# H7864.net
KiCad netlist of a schematic drawn in Altium Designer
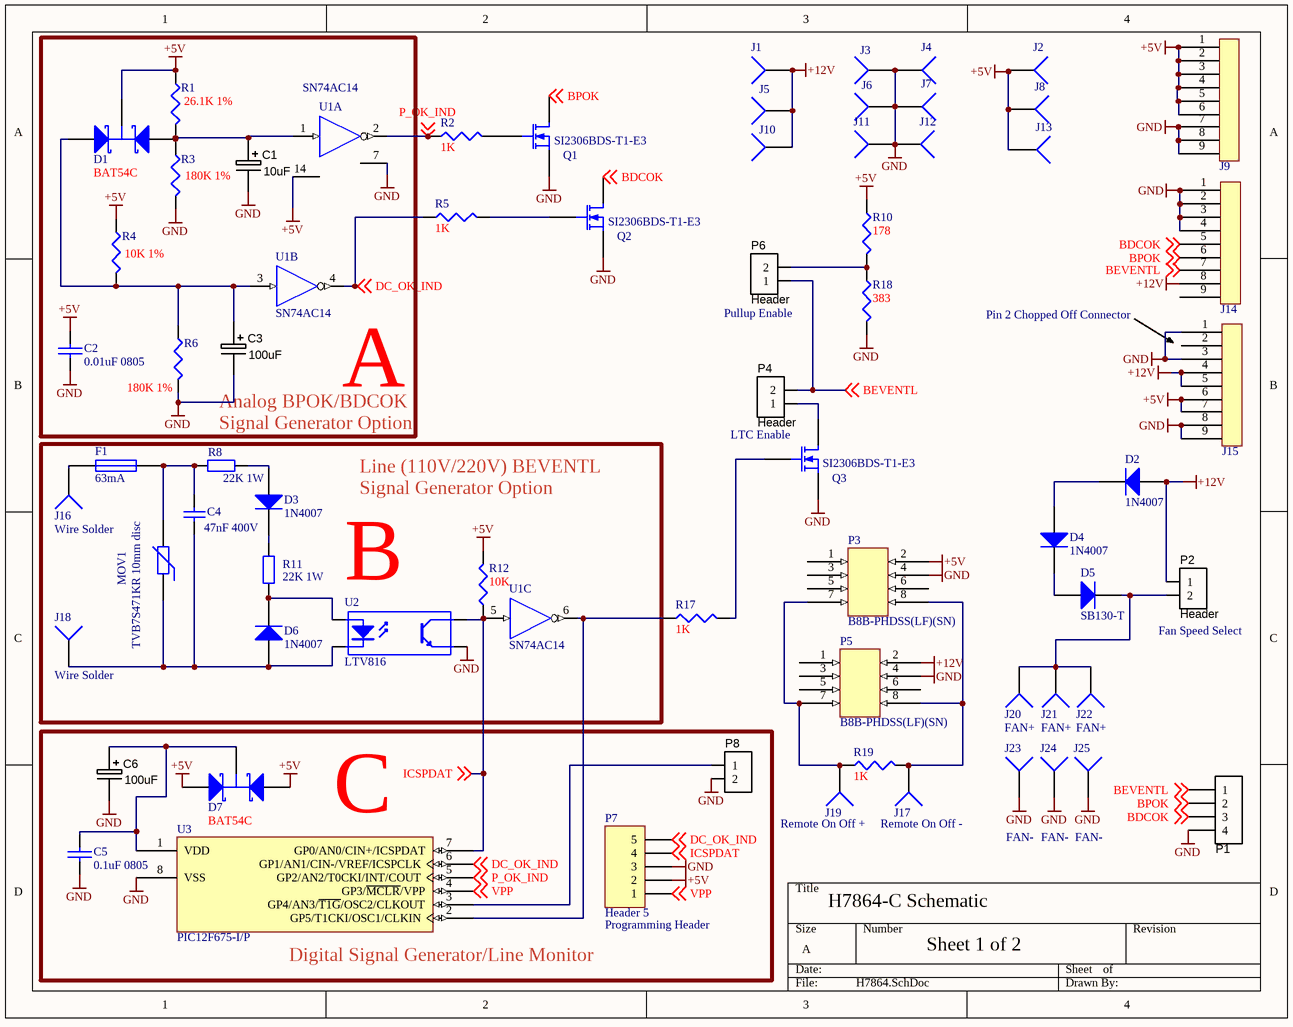
[diagram p0: H7864.SchDoc]

(export (version "E")
  (design (tool "Eeschema 10.0.6"))
  (components
    (comp (ref "C1")
      (value "10uF")
      (footprint "CAPMP3216X180N")
      (description "Capacitor SMD Tantalum 68uF 10% 6.3V EIA 3216-18")
      (fields (field (name "TOLERANCE") "±10%"))
      (libsource (lib "PBL - Capacitors") (part "CAPT_68u_3216_6V3"))
    )
    (comp (ref "C2")
      (value "0.01uF 0805")
      (footprint "C0805-S")
      (description "Capacitor")
      (fields (field (name "MANUFACTURER") "Vishay") (field (name "Comment") "VJ0805Y103JXAPW1BC"))
      (libsource (lib "TRA1404(DIFT2)") (part "CAP"))
    )
    (comp (ref "C3")
      (value "100uF")
      (footprint "CAPMP3216X180N")
      (description "Capacitor SMD Tantalum 68uF 10% 6.3V EIA 3216-18")
      (fields (field (name "TOLERANCE") "±10%"))
      (libsource (lib "PBL - Capacitors") (part "CAPT_68u_3216_6V3"))
    )
    (comp (ref "C4")
      (value "47nF 400V")
      (footprint "MKP-3381-15")
      (description "Capacitor")
      (fields (field (name "PUBLISHER") "Altium Limited"))
      (libsource (lib "Miscellaneous Devices") (part "Cap"))
    )
    (comp (ref "C5")
      (value "0.1uF 0805")
      (footprint "C0805-S")
      (description "Capacitor")
      (fields (field (name "MANUFACTURER") "Vishay") (field (name "Comment") "VJ0805Y103JXAPW1BC"))
      (libsource (lib "TRA1404(DIFT2)") (part "CAP"))
    )
    (comp (ref "C6")
      (value "100uF")
      (footprint "CAPMP3216X180N")
      (description "Capacitor SMD Tantalum 68uF 10% 6.3V EIA 3216-18")
      (fields (field (name "TOLERANCE") "±10%"))
      (libsource (lib "PBL - Capacitors") (part "CAPT_68u_3216_6V3"))
    )
    (comp (ref "D1")
      (value "BAT54C")
      (footprint "SOT23")
      (description "Schottky Barrier Double Diode")
      (fields (field (name "PUBLISHER") "Altium Limited"))
      (libsource (lib "Philips Discrete Diode - Schottky") (part "BAT54C"))
    )
    (comp (ref "D2")
      (value "1N4007")
      (footprint "DO-204AL")
      (description "1 Amp General Purpose Rectifier")
      (fields (field (name "PUBLISHER") "Altium Limited"))
      (libsource (lib "Miscellaneous Devices") (part "Diode 1N4007"))
    )
    (comp (ref "D3")
      (value "1N4007")
      (footprint "DO-204AL")
      (description "1 Amp General Purpose Rectifier")
      (fields (field (name "PUBLISHER") "Altium Limited"))
      (libsource (lib "Miscellaneous Devices") (part "Diode 1N4007"))
    )
    (comp (ref "D4")
      (value "1N4007")
      (footprint "DO-204AL")
      (description "1 Amp General Purpose Rectifier")
      (fields (field (name "PUBLISHER") "Altium Limited"))
      (libsource (lib "Miscellaneous Devices") (part "Diode 1N4007"))
    )
    (comp (ref "D5")
      (value "SB130-T")
      (footprint "DO-204AL")
      (description "1 Amp General Purpose Rectifier")
      (fields (field (name "PUBLISHER") "Altium Limited"))
      (libsource (lib "Miscellaneous Devices") (part "Diode 1N4007"))
    )
    (comp (ref "D6")
      (value "1N4007")
      (footprint "DO-204AL")
      (description "1 Amp General Purpose Rectifier")
      (fields (field (name "PUBLISHER") "Altium Limited"))
      (libsource (lib "Miscellaneous Devices") (part "Diode 1N4007"))
    )
    (comp (ref "D7")
      (value "BAT54C")
      (footprint "SOT23")
      (description "Schottky Barrier Double Diode")
      (fields (field (name "PUBLISHER") "Altium Limited"))
      (libsource (lib "Philips Discrete Diode - Schottky") (part "BAT54C"))
    )
    (comp (ref "F1")
      (value "63mA")
      (footprint "FUSE HOLDER 656")
      (description "Fuse Holder 65600001009  + cover 65900000009")
      (fields (field (name "PUBLISHER") "Altium Limited"))
      (libsource (lib "Miscellaneous Devices") (part "Fuse 1"))
    )
    (comp (ref "J1")
      (value "Wire Solder")
      (footprint "TP-THT-MULTI")
      (description "Socket")
      (fields (field (name "PUBLISHER") "Altium Limited"))
      (libsource (lib "Miscellaneous Connectors") (part "Socket"))
    )
    (comp (ref "J2")
      (value "Wire Solder")
      (footprint "TP-THT-MULTI")
      (description "Socket")
      (fields (field (name "PUBLISHER") "Altium Limited"))
      (libsource (lib "Miscellaneous Connectors") (part "Socket"))
    )
    (comp (ref "J3")
      (value "Wire Solder")
      (footprint "TP-THT-MULTI")
      (description "Socket")
      (fields (field (name "PUBLISHER") "Altium Limited"))
      (libsource (lib "Miscellaneous Connectors") (part "Socket"))
    )
    (comp (ref "J4")
      (value "Wire Solder")
      (footprint "TP-THT-MULTI")
      (description "Socket")
      (fields (field (name "PUBLISHER") "Altium Limited"))
      (libsource (lib "Miscellaneous Connectors") (part "Socket"))
    )
    (comp (ref "J5")
      (value "Wire Solder")
      (footprint "TP-THT-MULTI")
      (description "Socket")
      (fields (field (name "PUBLISHER") "Altium Limited"))
      (libsource (lib "Miscellaneous Connectors") (part "Socket"))
    )
    (comp (ref "J6")
      (value "Wire Solder")
      (footprint "TP-THT-MULTI")
      (description "Socket")
      (fields (field (name "PUBLISHER") "Altium Limited"))
      (libsource (lib "Miscellaneous Connectors") (part "Socket"))
    )
    (comp (ref "J7")
      (value "Wire Solder")
      (footprint "TP-THT-MULTI")
      (description "Socket")
      (fields (field (name "PUBLISHER") "Altium Limited"))
      (libsource (lib "Miscellaneous Connectors") (part "Socket"))
    )
    (comp (ref "J8")
      (value "Wire Solder")
      (footprint "TP-THT-MULTI")
      (description "Socket")
      (fields (field (name "PUBLISHER") "Altium Limited"))
      (libsource (lib "Miscellaneous Connectors") (part "Socket"))
    )
    (comp (ref "J9")
      (value "1-640385-9")
      (footprint "MTA156-9")
      (libsource (lib "Kanitti") (part "1-640385-9"))
    )
    (comp (ref "J10")
      (value "Wire Solder")
      (footprint "TP-THT-MULTI")
      (description "Socket")
      (fields (field (name "PUBLISHER") "Altium Limited"))
      (libsource (lib "Miscellaneous Connectors") (part "Socket"))
    )
    (comp (ref "J11")
      (value "Wire Solder")
      (footprint "TP-THT-MULTI")
      (description "Socket")
      (fields (field (name "PUBLISHER") "Altium Limited"))
      (libsource (lib "Miscellaneous Connectors") (part "Socket"))
    )
    (comp (ref "J12")
      (value "Wire Solder")
      (footprint "TP-THT-MULTI")
      (description "Socket")
      (fields (field (name "PUBLISHER") "Altium Limited"))
      (libsource (lib "Miscellaneous Connectors") (part "Socket"))
    )
    (comp (ref "J13")
      (value "Wire Solder")
      (footprint "TP-THT-MULTI")
      (description "Socket")
      (fields (field (name "PUBLISHER") "Altium Limited"))
      (libsource (lib "Miscellaneous Connectors") (part "Socket"))
    )
    (comp (ref "J14")
      (value "1-640385-9")
      (footprint "MTA156-9")
      (libsource (lib "Kanitti") (part "1-640385-9"))
    )
    (comp (ref "J15")
      (value "1-640385-9")
      (footprint "MTA156-9")
      (libsource (lib "Kanitti") (part "1-640385-9"))
    )
    (comp (ref "J16")
      (value "Wire Solder")
      (footprint "TP-THT-MULTI")
      (description "Socket")
      (fields (field (name "PUBLISHER") "Altium Limited"))
      (libsource (lib "Miscellaneous Connectors") (part "Socket"))
    )
    (comp (ref "J17")
      (value "Remote On Off -")
      (footprint "TP-THT-MULTI")
      (description "Socket")
      (fields (field (name "PUBLISHER") "Altium Limited"))
      (libsource (lib "Miscellaneous Connectors") (part "Socket"))
    )
    (comp (ref "J18")
      (value "Wire Solder")
      (footprint "TP-THT-MULTI")
      (description "Socket")
      (fields (field (name "PUBLISHER") "Altium Limited"))
      (libsource (lib "Miscellaneous Connectors") (part "Socket"))
    )
    (comp (ref "J19")
      (value "Remote On Off +")
      (footprint "TP-THT-MULTI")
      (description "Socket")
      (fields (field (name "PUBLISHER") "Altium Limited"))
      (libsource (lib "Miscellaneous Connectors") (part "Socket"))
    )
    (comp (ref "J20")
      (value "FAN+")
      (footprint "TP-THT-MULTI")
      (description "Socket")
      (fields (field (name "PUBLISHER") "Altium Limited"))
      (libsource (lib "Miscellaneous Connectors") (part "Socket"))
    )
    (comp (ref "J21")
      (value "FAN+")
      (footprint "TP-THT-MULTI")
      (description "Socket")
      (fields (field (name "PUBLISHER") "Altium Limited"))
      (libsource (lib "Miscellaneous Connectors") (part "Socket"))
    )
    (comp (ref "J22")
      (value "FAN+")
      (footprint "TP-THT-MULTI")
      (description "Socket")
      (fields (field (name "PUBLISHER") "Altium Limited"))
      (libsource (lib "Miscellaneous Connectors") (part "Socket"))
    )
    (comp (ref "J23")
      (value "FAN-")
      (footprint "TP-THT-MULTI")
      (description "Socket")
      (fields (field (name "PUBLISHER") "Altium Limited"))
      (libsource (lib "Miscellaneous Connectors") (part "Socket"))
    )
    (comp (ref "J24")
      (value "FAN-")
      (footprint "TP-THT-MULTI")
      (description "Socket")
      (fields (field (name "PUBLISHER") "Altium Limited"))
      (libsource (lib "Miscellaneous Connectors") (part "Socket"))
    )
    (comp (ref "J25")
      (value "FAN-")
      (footprint "TP-THT-MULTI")
      (description "Socket")
      (fields (field (name "PUBLISHER") "Altium Limited"))
      (libsource (lib "Miscellaneous Connectors") (part "Socket"))
    )
    (comp (ref "MOV1")
      (value "TVB7S471KR 10mm disc")
      (footprint "TVR1010")
      (description "Varistor (Voltage-Sensitive Resistor)")
      (fields (field (name "PUBLISHER") "Altium Limited"))
      (libsource (lib "Miscellaneous Devices") (part "Res Varistor"))
    )
    (comp (ref "P1")
      (value "Programmer")
      (footprint "HDR1X4_2.54mmp")
      (description "Header 4-pin")
      (libsource (lib "PBL - Connectors") (part "Header4P"))
    )
    (comp (ref "P2")
      (value "Header")
      (footprint "HDR_1x2_Offset")
      (description "Header, 2-pin")
      (libsource (lib "") (part "Header2P_1"))
    )
    (comp (ref "P3")
      (value "B8B-PHDSS(LF)(SN)")
      (footprint "B8B-PHDSS")
      (libsource (lib "Kanitti") (part "B8B-PHDSS(LF)(SN)"))
    )
    (comp (ref "P4")
      (value "Header")
      (footprint "HDR_1x2_Offset")
      (description "Header, 2-pin")
      (libsource (lib "PBL - Connectors") (part "Header2P"))
    )
    (comp (ref "P5")
      (value "B8B-PHDSS(LF)(SN)")
      (footprint "B8B-PHDSS")
      (libsource (lib "Kanitti") (part "B8B-PHDSS(LF)(SN)"))
    )
    (comp (ref "P6")
      (value "Header")
      (footprint "HDR_1x2_Offset")
      (description "Header, 2-pin")
      (libsource (lib "PBL - Connectors") (part "Header2P"))
    )
    (comp (ref "P7")
      (value "Header 5")
      (footprint "HDR1X5")
      (description "Header, 5-Pin")
      (fields (field (name "PUBLISHER") "Altium Limited"))
      (libsource (lib "Miscellaneous Connectors") (part "Header 5"))
    )
    (comp (ref "P8")
      (value "Header")
      (footprint "HDR_1x2_Offset")
      (description "Header, 2-pin")
      (libsource (lib "") (part "Header2P_1"))
    )
    (comp (ref "Q1")
      (value "SI2306BDS-T1-E3")
      (footprint "SOT23-3")
      (description "N-Channel MOSFET")
      (fields (field (name "MANUFACTURER") "Vishay") (field (name "PUBLISHER") "Altium Limited"))
      (libsource (lib "Miscellaneous Devices") (part "MOSFET-N"))
    )
    (comp (ref "Q2")
      (value "SI2306BDS-T1-E3")
      (footprint "SOT23-3")
      (description "N-Channel MOSFET")
      (fields (field (name "MANUFACTURER") "Vishay") (field (name "PUBLISHER") "Altium Limited"))
      (libsource (lib "Miscellaneous Devices") (part "MOSFET-N"))
    )
    (comp (ref "Q3")
      (value "SI2306BDS-T1-E3")
      (footprint "SOT23-3")
      (description "N-Channel MOSFET")
      (fields (field (name "MANUFACTURER") "Vishay") (field (name "PUBLISHER") "Altium Limited"))
      (libsource (lib "Miscellaneous Devices") (part "MOSFET-N"))
    )
    (comp (ref "R1")
      (value "26.1K 1%")
      (footprint "2012[0805]")
      (description "Resistor")
      (fields (field (name "PUBLISHER") "Altium Limited"))
      (libsource (lib "WS Controller") (part "Res3"))
    )
    (comp (ref "R2")
      (value "1K")
      (footprint "2012[0805]")
      (description "Resistor")
      (fields (field (name "Comment") "CRCW080547K0FKEA") (field (name "PUBLISHER") "Altium Limited"))
      (libsource (lib "WS Controller") (part "Res3"))
    )
    (comp (ref "R3")
      (value "180K 1%")
      (footprint "2012[0805]")
      (description "Resistor")
      (fields (field (name "PUBLISHER") "Altium Limited"))
      (libsource (lib "WS Controller") (part "Res3"))
    )
    (comp (ref "R4")
      (value "10K 1%")
      (footprint "2012[0805]")
      (description "Resistor")
      (fields (field (name "PUBLISHER") "Altium Limited"))
      (libsource (lib "WS Controller") (part "Res3"))
    )
    (comp (ref "R5")
      (value "1K")
      (footprint "2012[0805]")
      (description "Resistor")
      (fields (field (name "Comment") "CRCW080547K0FKEA") (field (name "PUBLISHER") "Altium Limited"))
      (libsource (lib "WS Controller") (part "Res3"))
    )
    (comp (ref "R6")
      (value "180K 1%")
      (footprint "2012[0805]")
      (description "Resistor")
      (fields (field (name "PUBLISHER") "Altium Limited"))
      (libsource (lib "WS Controller") (part "Res3"))
    )
    (comp (ref "R8")
      (value "22K 1W")
      (footprint "RESTH_AXIAL_MRA-05")
      (description "Resistor")
      (fields (field (name "PUBLISHER") "Altium Limited"))
      (libsource (lib "Miscellaneous Devices") (part "Res2"))
    )
    (comp (ref "R10")
      (value "178")
      (footprint "2012[0805]")
      (description "Resistor")
      (fields (field (name "Comment") "CRCW080547K0FKEA") (field (name "PUBLISHER") "Altium Limited"))
      (libsource (lib "WS Controller") (part "Res3"))
    )
    (comp (ref "R11")
      (value "22K 1W")
      (footprint "RESTH_AXIAL_MRA-05")
      (description "Resistor")
      (fields (field (name "PUBLISHER") "Altium Limited"))
      (libsource (lib "") (part "Res2_1"))
    )
    (comp (ref "R12")
      (value "10K")
      (footprint "2012[0805]")
      (description "Resistor")
      (fields (field (name "Comment") "CRCW080547K0FKEA") (field (name "PUBLISHER") "Altium Limited"))
      (libsource (lib "WS Controller") (part "Res3"))
    )
    (comp (ref "R17")
      (value "1K")
      (footprint "2012[0805]")
      (description "Resistor")
      (fields (field (name "Comment") "CRCW080547K0FKEA") (field (name "PUBLISHER") "Altium Limited"))
      (libsource (lib "WS Controller") (part "Res3"))
    )
    (comp (ref "R18")
      (value "383")
      (footprint "2012[0805]")
      (description "Resistor")
      (fields (field (name "Comment") "CRCW080547K0FKEA") (field (name "PUBLISHER") "Altium Limited"))
      (libsource (lib "WS Controller") (part "Res3"))
    )
    (comp (ref "R19")
      (value "1K")
      (footprint "2012[0805]")
      (description "Resistor")
      (fields (field (name "Comment") "CRCW080547K0FKEA") (field (name "PUBLISHER") "Altium Limited"))
      (libsource (lib "WS Controller") (part "Res3"))
    )
    (comp (ref "U1")
      (value "SN74AC14")
      (footprint "J014C")
      (description "Hex Schmitt-Trigger Inverter")
      (fields (field (name "PUBLISHER") "Altium Limited"))
      (libsource (lib "TI Logic Gate 1") (part "SN74AHCT14D"))
    )
    (comp (ref "U2")
      (value "LTV816")
      (footprint "DIP-4")
      (description "4-Pin Phototransistor Optocoupler")
      (fields (field (name "PUBLISHER") "Altium Limited"))
      (libsource (lib "Miscellaneous Devices") (part "Optoisolator1"))
    )
    (comp (ref "U3")
      (value "PIC12F675-I/P")
      (footprint "DIP8-300")
      (description "FLASH-Based 8-Bit CMOS Microcontroller, 10-Bit A/D, 8-Pin PDIP, Industrial Temperature")
      (fields (field (name "PUBLISHER") "Altium Limited"))
      (libsource (lib "Microchip Microcontroller 8-Bit PIC12") (part "PIC12F675-I/P"))
    )
  )
  (nets
    (net (code "1") (name "+5V") (class "Default")
      (node (ref "C2") (pin "2") (pinfunction "2_2") (pintype "passive"))
      (node (ref "D1") (pin "3") (pinfunction "K_3") (pintype "passive"))
      (node (ref "D7") (pin "1") (pinfunction "A1_1") (pintype "passive"))
      (node (ref "D7") (pin "2") (pinfunction "A2_2") (pintype "passive"))
      (node (ref "J13") (pin "1") (pinfunction "1_1") (pintype "passive"))
      (node (ref "J15") (pin "6") (pinfunction "6_6") (pintype "passive"))
      (node (ref "J15") (pin "7") (pinfunction "7_7") (pintype "passive"))
      (node (ref "J2") (pin "1") (pinfunction "1_1") (pintype "passive"))
      (node (ref "J8") (pin "1") (pinfunction "1_1") (pintype "passive"))
      (node (ref "J9") (pin "1") (pinfunction "1_1") (pintype "passive"))
      (node (ref "J9") (pin "2") (pinfunction "2_2") (pintype "passive"))
      (node (ref "J9") (pin "3") (pinfunction "3_3") (pintype "passive"))
      (node (ref "J9") (pin "4") (pinfunction "4_4") (pintype "passive"))
      (node (ref "J9") (pin "5") (pinfunction "5_5") (pintype "passive"))
      (node (ref "J9") (pin "6") (pinfunction "6_6") (pintype "passive"))
      (node (ref "P3") (pin "2") (pintype "input"))
      (node (ref "P7") (pin "2") (pinfunction "2_2") (pintype "passive"))
      (node (ref "R1") (pin "1") (pinfunction "1_1") (pintype "passive"))
      (node (ref "R10") (pin "1") (pinfunction "1_1") (pintype "passive"))
      (node (ref "R12") (pin "2") (pinfunction "2_2") (pintype "passive"))
      (node (ref "R4") (pin "1") (pinfunction "1_1") (pintype "passive"))
      (node (ref "U1") (pin "14") (pinfunction "VCC_14") (pintype "power_in"))
    )
    (net (code "2") (name "+12V") (class "Default")
      (node (ref "D2") (pin "1") (pinfunction "A_1") (pintype "passive"))
      (node (ref "J1") (pin "1") (pinfunction "1_1") (pintype "passive"))
      (node (ref "J10") (pin "1") (pinfunction "1_1") (pintype "passive"))
      (node (ref "J14") (pin "8") (pinfunction "8_8") (pintype "passive"))
      (node (ref "J15") (pin "4") (pinfunction "4_4") (pintype "passive"))
      (node (ref "J15") (pin "5") (pinfunction "5_5") (pintype "passive"))
      (node (ref "J5") (pin "1") (pinfunction "1_1") (pintype "passive"))
      (node (ref "P2") (pin "1") (pinfunction "1_1") (pintype "passive"))
      (node (ref "P5") (pin "2") (pintype "input"))
    )
    (net (code "3") (name "BDCOK") (class "Default")
      (node (ref "J14") (pin "5") (pinfunction "5_5") (pintype "passive"))
      (node (ref "P1") (pin "3") (pinfunction "3_3") (pintype "passive"))
      (node (ref "Q2") (pin "3") (pinfunction "D_3") (pintype "passive"))
    )
    (net (code "4") (name "BEVENTL") (class "Default")
      (node (ref "J14") (pin "7") (pinfunction "7_7") (pintype "passive"))
      (node (ref "P1") (pin "1") (pinfunction "1_1") (pintype "passive"))
      (node (ref "P4") (pin "2") (pinfunction "2_2") (pintype "passive"))
      (node (ref "P6") (pin "1") (pinfunction "1_1") (pintype "passive"))
    )
    (net (code "5") (name "BPOK") (class "Default")
      (node (ref "J14") (pin "6") (pinfunction "6_6") (pintype "passive"))
      (node (ref "P1") (pin "2") (pinfunction "2_2") (pintype "passive"))
      (node (ref "Q1") (pin "3") (pinfunction "D_3") (pintype "passive"))
    )
    (net (code "6") (name "DC_OK_IND") (class "Default")
      (node (ref "P7") (pin "5") (pinfunction "5_5") (pintype "passive"))
      (node (ref "R5") (pin "1") (pinfunction "1_1") (pintype "passive"))
      (node (ref "U1") (pin "4") (pinfunction "Y_4") (pintype "output"))
      (node (ref "U3") (pin "6") (pinfunction "GP1/AN1/CIN-/VREF/ICSPCLK_6") (pintype "bidirectional"))
    )
    (net (code "7") (name "GND") (class "Default")
      (node (ref "C1") (pin "2") (pintype "passive"))
      (node (ref "C2") (pin "1") (pinfunction "1_1") (pintype "passive"))
      (node (ref "C3") (pin "2") (pintype "passive"))
      (node (ref "C5") (pin "1") (pinfunction "1_1") (pintype "passive"))
      (node (ref "C6") (pin "2") (pintype "passive"))
      (node (ref "J11") (pin "1") (pinfunction "1_1") (pintype "passive"))
      (node (ref "J12") (pin "1") (pinfunction "1_1") (pintype "passive"))
      (node (ref "J14") (pin "1") (pinfunction "1_1") (pintype "passive"))
      (node (ref "J14") (pin "2") (pinfunction "2_2") (pintype "passive"))
      (node (ref "J14") (pin "3") (pinfunction "3_3") (pintype "passive"))
      (node (ref "J14") (pin "4") (pinfunction "4_4") (pintype "passive"))
      (node (ref "J15") (pin "1") (pinfunction "1_1") (pintype "passive"))
      (node (ref "J15") (pin "3") (pinfunction "3_3") (pintype "passive"))
      (node (ref "J15") (pin "8") (pinfunction "8_8") (pintype "passive"))
      (node (ref "J15") (pin "9") (pinfunction "9_9") (pintype "passive"))
      (node (ref "J23") (pin "1") (pinfunction "1_1") (pintype "passive"))
      (node (ref "J24") (pin "1") (pinfunction "1_1") (pintype "passive"))
      (node (ref "J25") (pin "1") (pinfunction "1_1") (pintype "passive"))
      (node (ref "J3") (pin "1") (pinfunction "1_1") (pintype "passive"))
      (node (ref "J4") (pin "1") (pinfunction "1_1") (pintype "passive"))
      (node (ref "J6") (pin "1") (pinfunction "1_1") (pintype "passive"))
      (node (ref "J7") (pin "1") (pinfunction "1_1") (pintype "passive"))
      (node (ref "J9") (pin "7") (pinfunction "7_7") (pintype "passive"))
      (node (ref "J9") (pin "8") (pinfunction "8_8") (pintype "passive"))
      (node (ref "J9") (pin "9") (pinfunction "9_9") (pintype "passive"))
      (node (ref "P1") (pin "4") (pinfunction "4_4") (pintype "passive"))
      (node (ref "P3") (pin "4") (pintype "input"))
      (node (ref "P5") (pin "4") (pintype "input"))
      (node (ref "P7") (pin "3") (pinfunction "3_3") (pintype "passive"))
      (node (ref "P8") (pin "2") (pinfunction "2_2") (pintype "passive"))
      (node (ref "Q1") (pin "2") (pinfunction "S_2") (pintype "passive"))
      (node (ref "Q2") (pin "2") (pinfunction "S_2") (pintype "passive"))
      (node (ref "Q3") (pin "2") (pinfunction "S_2") (pintype "passive"))
      (node (ref "R18") (pin "2") (pinfunction "2_2") (pintype "passive"))
      (node (ref "R3") (pin "2") (pinfunction "2_2") (pintype "passive"))
      (node (ref "R6") (pin "2") (pinfunction "2_2") (pintype "passive"))
      (node (ref "U1") (pin "7") (pinfunction "GND_7") (pintype "power_in"))
      (node (ref "U2") (pin "3") (pinfunction "E_3") (pintype "passive"))
      (node (ref "U3") (pin "8") (pinfunction "VSS_8") (pintype "power_in"))
    )
    (net (code "8") (name "ICSPDAT") (class "Default")
      (node (ref "P7") (pin "4") (pinfunction "4_4") (pintype "passive"))
      (node (ref "R12") (pin "1") (pinfunction "1_1") (pintype "passive"))
      (node (ref "U1") (pin "5") (pinfunction "A_5") (pintype "input"))
      (node (ref "U2") (pin "4") (pinfunction "C_4") (pintype "passive"))
      (node (ref "U3") (pin "7") (pinfunction "GP0/AN0/CIN+/ICSPDAT_7") (pintype "bidirectional"))
    )
    (net (code "9") (name "Net-(C4-Pad2)") (class "Default")
      (node (ref "C4") (pin "2") (pinfunction "2_2") (pintype "passive"))
      (node (ref "F1") (pin "1") (pinfunction "1_1") (pintype "passive"))
      (node (ref "MOV1") (pin "2") (pinfunction "2_2") (pintype "passive"))
      (node (ref "R8") (pin "1") (pinfunction "1_1") (pintype "passive"))
    )
    (net (code "10") (name "Net-(D1-A1)") (class "Default")
      (node (ref "C3") (pin "1") (pintype "passive"))
      (node (ref "D1") (pin "1") (pinfunction "A1_1") (pintype "passive"))
      (node (ref "R4") (pin "2") (pinfunction "2_2") (pintype "passive"))
      (node (ref "R6") (pin "1") (pinfunction "1_1") (pintype "passive"))
      (node (ref "U1") (pin "3") (pinfunction "A_3") (pintype "input"))
    )
    (net (code "11") (name "Net-(D1-A2)") (class "Default")
      (node (ref "C1") (pin "1") (pintype "passive"))
      (node (ref "D1") (pin "2") (pinfunction "A2_2") (pintype "passive"))
      (node (ref "R1") (pin "2") (pinfunction "2_2") (pintype "passive"))
      (node (ref "R3") (pin "1") (pinfunction "1_1") (pintype "passive"))
      (node (ref "U1") (pin "1") (pinfunction "A_1") (pintype "input"))
    )
    (net (code "12") (name "Net-(D2-K)") (class "Default")
      (node (ref "D2") (pin "2") (pinfunction "K_2") (pintype "passive"))
      (node (ref "D4") (pin "1") (pinfunction "A_1") (pintype "passive"))
    )
    (net (code "13") (name "Net-(D3-A)") (class "Default")
      (node (ref "D3") (pin "1") (pinfunction "A_1") (pintype "passive"))
      (node (ref "R8") (pin "2") (pinfunction "2_2") (pintype "passive"))
    )
    (net (code "14") (name "Net-(D3-K)") (class "Default")
      (node (ref "D3") (pin "2") (pinfunction "K_2") (pintype "passive"))
      (node (ref "R11") (pin "1") (pinfunction "1_1") (pintype "passive"))
    )
    (net (code "15") (name "Net-(D4-K)") (class "Default")
      (node (ref "D4") (pin "2") (pinfunction "K_2") (pintype "passive"))
      (node (ref "D5") (pin "1") (pinfunction "A_1") (pintype "passive"))
    )
    (net (code "16") (name "Net-(D5-K)") (class "Default")
      (node (ref "D5") (pin "2") (pinfunction "K_2") (pintype "passive"))
      (node (ref "J20") (pin "1") (pinfunction "1_1") (pintype "passive"))
      (node (ref "J21") (pin "1") (pinfunction "1_1") (pintype "passive"))
      (node (ref "J22") (pin "1") (pinfunction "1_1") (pintype "passive"))
      (node (ref "P2") (pin "2") (pinfunction "2_2") (pintype "passive"))
    )
    (net (code "17") (name "Net-(D6-A)") (class "Default")
      (node (ref "C4") (pin "1") (pinfunction "1_1") (pintype "passive"))
      (node (ref "D6") (pin "1") (pinfunction "A_1") (pintype "passive"))
      (node (ref "J18") (pin "1") (pinfunction "1_1") (pintype "passive"))
      (node (ref "MOV1") (pin "1") (pinfunction "1_1") (pintype "passive"))
      (node (ref "U2") (pin "2") (pinfunction "K_2") (pintype "passive"))
    )
    (net (code "18") (name "Net-(D6-K)") (class "Default")
      (node (ref "D6") (pin "2") (pinfunction "K_2") (pintype "passive"))
      (node (ref "R11") (pin "2") (pinfunction "2_2") (pintype "passive"))
      (node (ref "U2") (pin "1") (pinfunction "A_1") (pintype "passive"))
    )
    (net (code "19") (name "Net-(D7-K)") (class "Default")
      (node (ref "C5") (pin "2") (pinfunction "2_2") (pintype "passive"))
      (node (ref "C6") (pin "1") (pintype "passive"))
      (node (ref "D7") (pin "3") (pinfunction "K_3") (pintype "passive"))
      (node (ref "U3") (pin "1") (pinfunction "VDD_1") (pintype "power_in"))
    )
    (net (code "20") (name "Net-(F1-Pad2)") (class "Default")
      (node (ref "F1") (pin "2") (pinfunction "2_2") (pintype "passive"))
      (node (ref "J16") (pin "1") (pinfunction "1_1") (pintype "passive"))
    )
    (net (code "21") (name "Net-(J17-Pad1)") (class "Default")
      (node (ref "J17") (pin "1") (pinfunction "1_1") (pintype "passive"))
      (node (ref "P3") (pin "8") (pintype "input"))
      (node (ref "P5") (pin "8") (pintype "input"))
      (node (ref "R19") (pin "2") (pinfunction "2_2") (pintype "passive"))
    )
    (net (code "22") (name "Net-(J19-Pad1)") (class "Default")
      (node (ref "J19") (pin "1") (pinfunction "1_1") (pintype "passive"))
      (node (ref "P3") (pin "7") (pintype "input"))
      (node (ref "P5") (pin "7") (pintype "input"))
      (node (ref "R19") (pin "1") (pinfunction "1_1") (pintype "passive"))
    )
    (net (code "23") (name "Net-(P6-Pad2)") (class "Default")
      (node (ref "P6") (pin "2") (pinfunction "2_2") (pintype "passive"))
      (node (ref "R10") (pin "2") (pinfunction "2_2") (pintype "passive"))
      (node (ref "R18") (pin "1") (pinfunction "1_1") (pintype "passive"))
    )
    (net (code "24") (name "Net-(Q1-G)") (class "Default")
      (node (ref "Q1") (pin "1") (pinfunction "G_1") (pintype "passive"))
      (node (ref "R2") (pin "2") (pinfunction "2_2") (pintype "passive"))
    )
    (net (code "25") (name "Net-(Q2-G)") (class "Default")
      (node (ref "Q2") (pin "1") (pinfunction "G_1") (pintype "passive"))
      (node (ref "R5") (pin "2") (pinfunction "2_2") (pintype "passive"))
    )
    (net (code "26") (name "Net-(Q3-D)") (class "Default")
      (node (ref "P4") (pin "1") (pinfunction "1_1") (pintype "passive"))
      (node (ref "Q3") (pin "3") (pinfunction "D_3") (pintype "passive"))
    )
    (net (code "27") (name "Net-(Q3-G)") (class "Default")
      (node (ref "Q3") (pin "1") (pinfunction "G_1") (pintype "passive"))
      (node (ref "R17") (pin "2") (pinfunction "2_2") (pintype "passive"))
    )
    (net (code "28") (name "Net-(U1C-Y)") (class "Default")
      (node (ref "R17") (pin "1") (pinfunction "1_1") (pintype "passive"))
      (node (ref "U1") (pin "6") (pinfunction "Y_6") (pintype "output"))
      (node (ref "U3") (pin "2") (pinfunction "GP5/T1CKI/OSC1/CLKIN_2") (pintype "bidirectional"))
    )
    (net (code "29") (name "Net-(U3-GP4{slash}AN3{slash}~{T1G}{slash}OSC2{slash}CLKOUT)") (class "Default")
      (node (ref "P8") (pin "1") (pinfunction "1_1") (pintype "passive"))
      (node (ref "U3") (pin "3") (pinfunction "GP4/AN3/~{T1G}/OSC2/CLKOUT_3") (pintype "bidirectional"))
    )
    (net (code "30") (name "P_OK_IND") (class "Default")
      (node (ref "R2") (pin "1") (pinfunction "1_1") (pintype "passive"))
      (node (ref "U1") (pin "2") (pinfunction "Y_2") (pintype "output"))
      (node (ref "U3") (pin "5") (pinfunction "GP2/AN2/T0CKI/INT/COUT_5") (pintype "bidirectional"))
    )
    (net (code "31") (name "VCC") (class "Default")
      (node (ref "U1") (pin "14") (pinfunction "VCC_14") (pintype "power_in"))
    )
    (net (code "32") (name "VPP") (class "Default")
      (node (ref "P7") (pin "1") (pinfunction "1_1") (pintype "passive"))
      (node (ref "U3") (pin "4") (pinfunction "GP3/~{MCLR}/VPP_4") (pintype "bidirectional"))
    )
    (net (code "33") (name "unconnected-(J14-Pad9)") (class "Default")
      (node (ref "J14") (pin "9") (pinfunction "9_9") (pintype "passive"))
    )
    (net (code "34") (name "unconnected-(J15-Pad2)") (class "Default")
      (node (ref "J15") (pin "2") (pinfunction "2_2") (pintype "passive"))
    )
    (net (code "35") (name "unconnected-(P3-Pad1)") (class "Default")
      (node (ref "P3") (pin "1") (pintype "input"))
    )
    (net (code "36") (name "unconnected-(P3-Pad3)") (class "Default")
      (node (ref "P3") (pin "3") (pintype "input"))
    )
    (net (code "37") (name "unconnected-(P3-Pad5)") (class "Default")
      (node (ref "P3") (pin "5") (pintype "input"))
    )
    (net (code "38") (name "unconnected-(P3-Pad6)") (class "Default")
      (node (ref "P3") (pin "6") (pintype "input"))
    )
    (net (code "39") (name "unconnected-(P5-Pad1)") (class "Default")
      (node (ref "P5") (pin "1") (pintype "input"))
    )
    (net (code "40") (name "unconnected-(P5-Pad3)") (class "Default")
      (node (ref "P5") (pin "3") (pintype "input"))
    )
    (net (code "41") (name "unconnected-(P5-Pad5)") (class "Default")
      (node (ref "P5") (pin "5") (pintype "input"))
    )
    (net (code "42") (name "unconnected-(P5-Pad6)") (class "Default")
      (node (ref "P5") (pin "6") (pintype "input"))
    )
  )
)
